# 04_Driver.net
KiCad netlist of a schematic drawn in Altium Designer
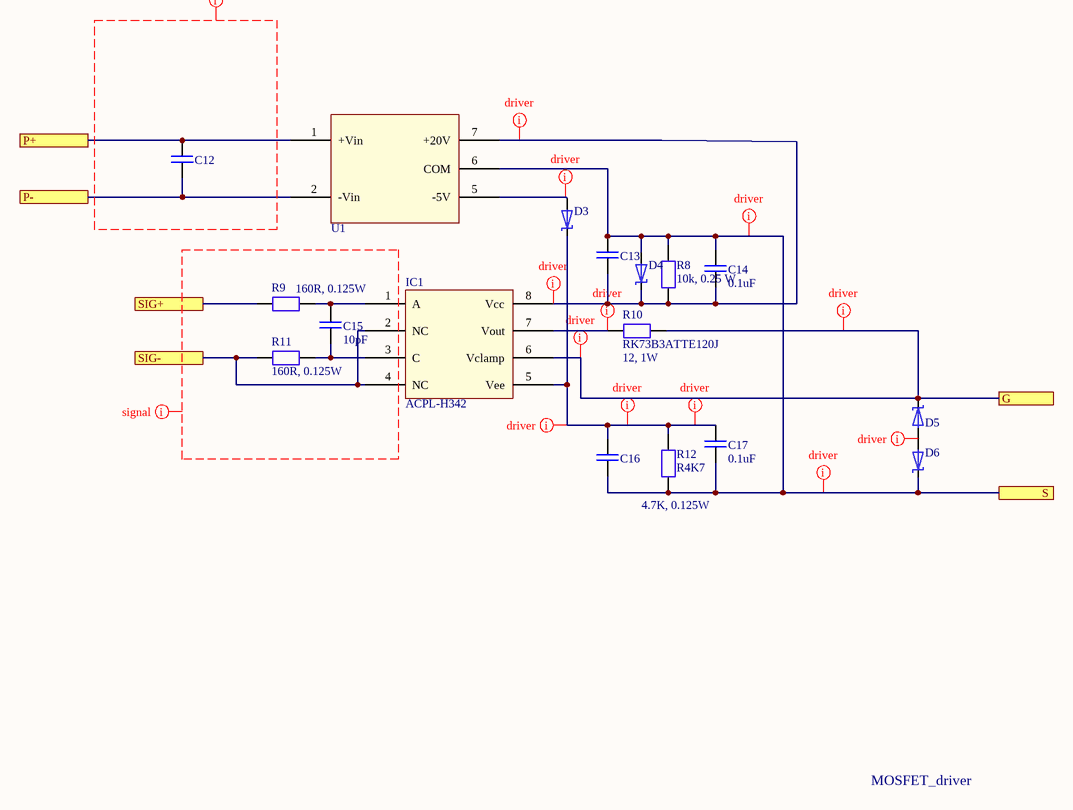
[diagram p0: 04_Driver.SchDoc]

(export (version "E")
  (design (tool "Eeschema 10.0.6"))
  (components
    (comp (ref "C12")
      (value "Cer_large")
      (footprint "CAPC3227X25N")
      (libsource (lib "capacitors") (part "Cer_large"))
    )
    (comp (ref "C13")
      (value "Cer_large")
      (footprint "CAPC3227X25N")
      (libsource (lib "capacitors") (part "Cer_large"))
    )
    (comp (ref "C14")
      (value "0.1uF")
      (footprint "C_0805")
      (description "0.1u, 50V")
      (fields (field (name "MANUFACTURER") "Kemet") (field (name "Comment") "C0805C104K5RAC"))
      (libsource (lib "capacitors") (part "C0805C104K5RAC"))
    )
    (comp (ref "C15")
      (value "10pF")
      (footprint "C_0805")
      (description "10p, 100V")
      (fields (field (name "MANUFACTURER") "Kemet") (field (name "Comment") "C0805C100J1GAC"))
      (libsource (lib "capacitors") (part "C0805C100J1GAC"))
    )
    (comp (ref "C16")
      (value "Cer_large")
      (footprint "CAPC3227X25N")
      (libsource (lib "capacitors") (part "Cer_large"))
    )
    (comp (ref "C17")
      (value "0.1uF")
      (footprint "C_0805")
      (description "0.1u, 50V")
      (fields (field (name "MANUFACTURER") "Kemet") (field (name "Comment") "C0805C104K5RAC"))
      (libsource (lib "capacitors") (part "C0805C104K5RAC"))
    )
    (comp (ref "D3")
      (value "Zener_1.8V")
      (footprint "SOD123")
      (description "Zener diode")
      (libsource (lib "Library") (part "Zener_1.8V"))
    )
    (comp (ref "D4")
      (value "DZ2J220M0L")
      (footprint "SOD323F")
      (libsource (lib "Library") (part "DZ2J220M0L"))
    )
    (comp (ref "D5")
      (value "MMSZ4678T1G")
      (footprint "CAPM3216X18N")
      (description "6V, 500mW, Zener Diodes")
      (fields (field (name "MANUFACTURER") "ON Semiconductor") (field (name "PARTNUMBER") "MMSZ5233BT1G"))
      (libsource (lib "Universal_Control_Measure_Board") (part "Zener_MMSZ5233BT1G"))
    )
    (comp (ref "D6")
      (value "MMSZ4678T1G")
      (footprint "CAPM3216X18N")
      (description "6V, 500mW, Zener Diodes")
      (fields (field (name "MANUFACTURER") "ON Semiconductor") (field (name "PARTNUMBER") "MMSZ5233BT1G"))
      (libsource (lib "Universal_Control_Measure_Board") (part "Zener_MMSZ5233BT1G"))
    )
    (comp (ref "IC1")
      (value "ACPL-H342")
      (footprint "SOIC127P970X330-8N")
      (fields (field (name "MANUFACTURER") "Avago") (field (name "PUBLISHER") "*"))
      (libsource (lib "Schlib1") (part "ACPL-H342"))
    )
    (comp (ref "R8")
      (value "10k, 0.25 W")
      (footprint "SMD_1206")
      (fields (field (name "MANUFACTURER") "KOA") (field (name "Comment") "RK73H2BTTD1002F"))
      (libsource (lib "resistors") (part "RK73H2BTTD1002F"))
    )
    (comp (ref "R9")
      (value "160R, 0.125W")
      (footprint "SMD_0805")
      (fields (field (name "MANUFACTURER") "KOA") (field (name "Comment") "RK73H2ATTD1600F"))
      (libsource (lib "resistors") (part "RK73H2ATTD1600F"))
    )
    (comp (ref "R10")
      (value "RK73B3ATTE120J")
      (footprint "SMD_2512")
      (fields (field (name "MANUFACTURER") "KOA") (field (name "ALTIUM_VALUE") "12, 1W"))
      (libsource (lib "resistors") (part "RK73B3ATTE120J"))
    )
    (comp (ref "R11")
      (value "160R, 0.125W")
      (footprint "SMD_0805")
      (fields (field (name "MANUFACTURER") "KOA") (field (name "Comment") "RK73H2ATTD1600F"))
      (libsource (lib "resistors") (part "RK73H2ATTD1600F"))
    )
    (comp (ref "R12")
      (value "R4K7")
      (footprint "smd_0603")
      (fields (field (name "ALTIUM_VALUE") "4.7K, 0.125W"))
      (libsource (lib "resistors") (part "R4K7"))
    )
    (comp (ref "U1")
      (value "MGJ2D242005SC")
      (footprint "MGJ2")
      (libsource (lib "Library") (part "MGJ2D242005SC"))
    )
  )
  (nets
    (net (code "1") (name "/G") (class "Default")
      (node (ref "D5") (pin "1") (pinfunction "1_1") (pintype "passive"))
      (node (ref "IC1") (pin "6") (pinfunction "Vclamp_6") (pintype "passive"))
      (node (ref "R10") (pin "2") (pinfunction "2_2") (pintype "passive"))
    )
    (net (code "2") (name "/P+") (class "Default")
      (node (ref "C12") (pin "1") (pinfunction "1_1") (pintype "passive"))
      (node (ref "U1") (pin "1") (pinfunction "+Vin_1") (pintype "passive"))
    )
    (net (code "3") (name "/P-") (class "Default")
      (node (ref "C12") (pin "2") (pinfunction "2_2") (pintype "passive"))
      (node (ref "U1") (pin "2") (pinfunction "-Vin_2") (pintype "passive"))
    )
    (net (code "4") (name "/S") (class "Default")
      (node (ref "C13") (pin "1") (pinfunction "1_1") (pintype "passive"))
      (node (ref "C14") (pin "1") (pinfunction "1_1") (pintype "passive"))
      (node (ref "C16") (pin "2") (pinfunction "2_2") (pintype "passive"))
      (node (ref "C17") (pin "2") (pinfunction "2_2") (pintype "passive"))
      (node (ref "D4") (pin "1") (pinfunction "1_1") (pintype "passive"))
      (node (ref "D6") (pin "1") (pinfunction "1_1") (pintype "passive"))
      (node (ref "R12") (pin "1") (pinfunction "1_1") (pintype "passive"))
      (node (ref "R8") (pin "2") (pinfunction "2_2") (pintype "passive"))
      (node (ref "U1") (pin "6") (pinfunction "COM_6") (pintype "passive"))
    )
    (net (code "5") (name "/SIG+") (class "Default")
      (node (ref "R9") (pin "1") (pinfunction "1_1") (pintype "passive"))
    )
    (net (code "6") (name "/SIG-") (class "Default")
      (node (ref "IC1") (pin "2") (pinfunction "NC_2") (pintype "passive"))
      (node (ref "IC1") (pin "4") (pinfunction "NC_4") (pintype "passive"))
      (node (ref "R11") (pin "1") (pinfunction "1_1") (pintype "passive"))
    )
    (net (code "7") (name "Net-(D5-Pad2)") (class "Default")
      (node (ref "D5") (pin "2") (pinfunction "2_2") (pintype "passive"))
      (node (ref "D6") (pin "2") (pinfunction "2_2") (pintype "passive"))
    )
    (net (code "8") (name "Net-(IC1-A)") (class "Default")
      (node (ref "C15") (pin "1") (pinfunction "1_1") (pintype "passive"))
      (node (ref "IC1") (pin "1") (pinfunction "A_1") (pintype "passive"))
      (node (ref "R9") (pin "2") (pinfunction "2_2") (pintype "passive"))
    )
    (net (code "9") (name "Net-(IC1-C)") (class "Default")
      (node (ref "C15") (pin "2") (pinfunction "2_2") (pintype "passive"))
      (node (ref "IC1") (pin "3") (pinfunction "C_3") (pintype "passive"))
      (node (ref "R11") (pin "2") (pinfunction "2_2") (pintype "passive"))
    )
    (net (code "10") (name "Net-(IC1-Vcc)") (class "Default")
      (node (ref "C13") (pin "2") (pinfunction "2_2") (pintype "passive"))
      (node (ref "C14") (pin "2") (pinfunction "2_2") (pintype "passive"))
      (node (ref "D4") (pin "2") (pinfunction "2_2") (pintype "passive"))
      (node (ref "IC1") (pin "8") (pinfunction "Vcc_8") (pintype "passive"))
      (node (ref "R8") (pin "1") (pinfunction "1_1") (pintype "passive"))
      (node (ref "U1") (pin "7") (pinfunction "+20V_7") (pintype "passive"))
    )
    (net (code "11") (name "Net-(IC1-Vee)") (class "Default")
      (node (ref "C16") (pin "1") (pinfunction "1_1") (pintype "passive"))
      (node (ref "C17") (pin "1") (pinfunction "1_1") (pintype "passive"))
      (node (ref "D3") (pin "2") (pinfunction "2_2") (pintype "passive"))
      (node (ref "IC1") (pin "5") (pinfunction "Vee_5") (pintype "passive"))
      (node (ref "R12") (pin "2") (pinfunction "2_2") (pintype "passive"))
    )
    (net (code "12") (name "Net-(IC1-Vout)") (class "Default")
      (node (ref "IC1") (pin "7") (pinfunction "Vout_7") (pintype "passive"))
      (node (ref "R10") (pin "1") (pinfunction "1_1") (pintype "passive"))
    )
    (net (code "13") (name "Net-(U1--5V)") (class "Default")
      (node (ref "D3") (pin "1") (pinfunction "1_1") (pintype "passive"))
      (node (ref "U1") (pin "5") (pinfunction "-5V_5") (pintype "passive"))
    )
  )
)
